# lab2_vodorezov_buck.net
KiCad netlist of a schematic drawn in Altium Designer
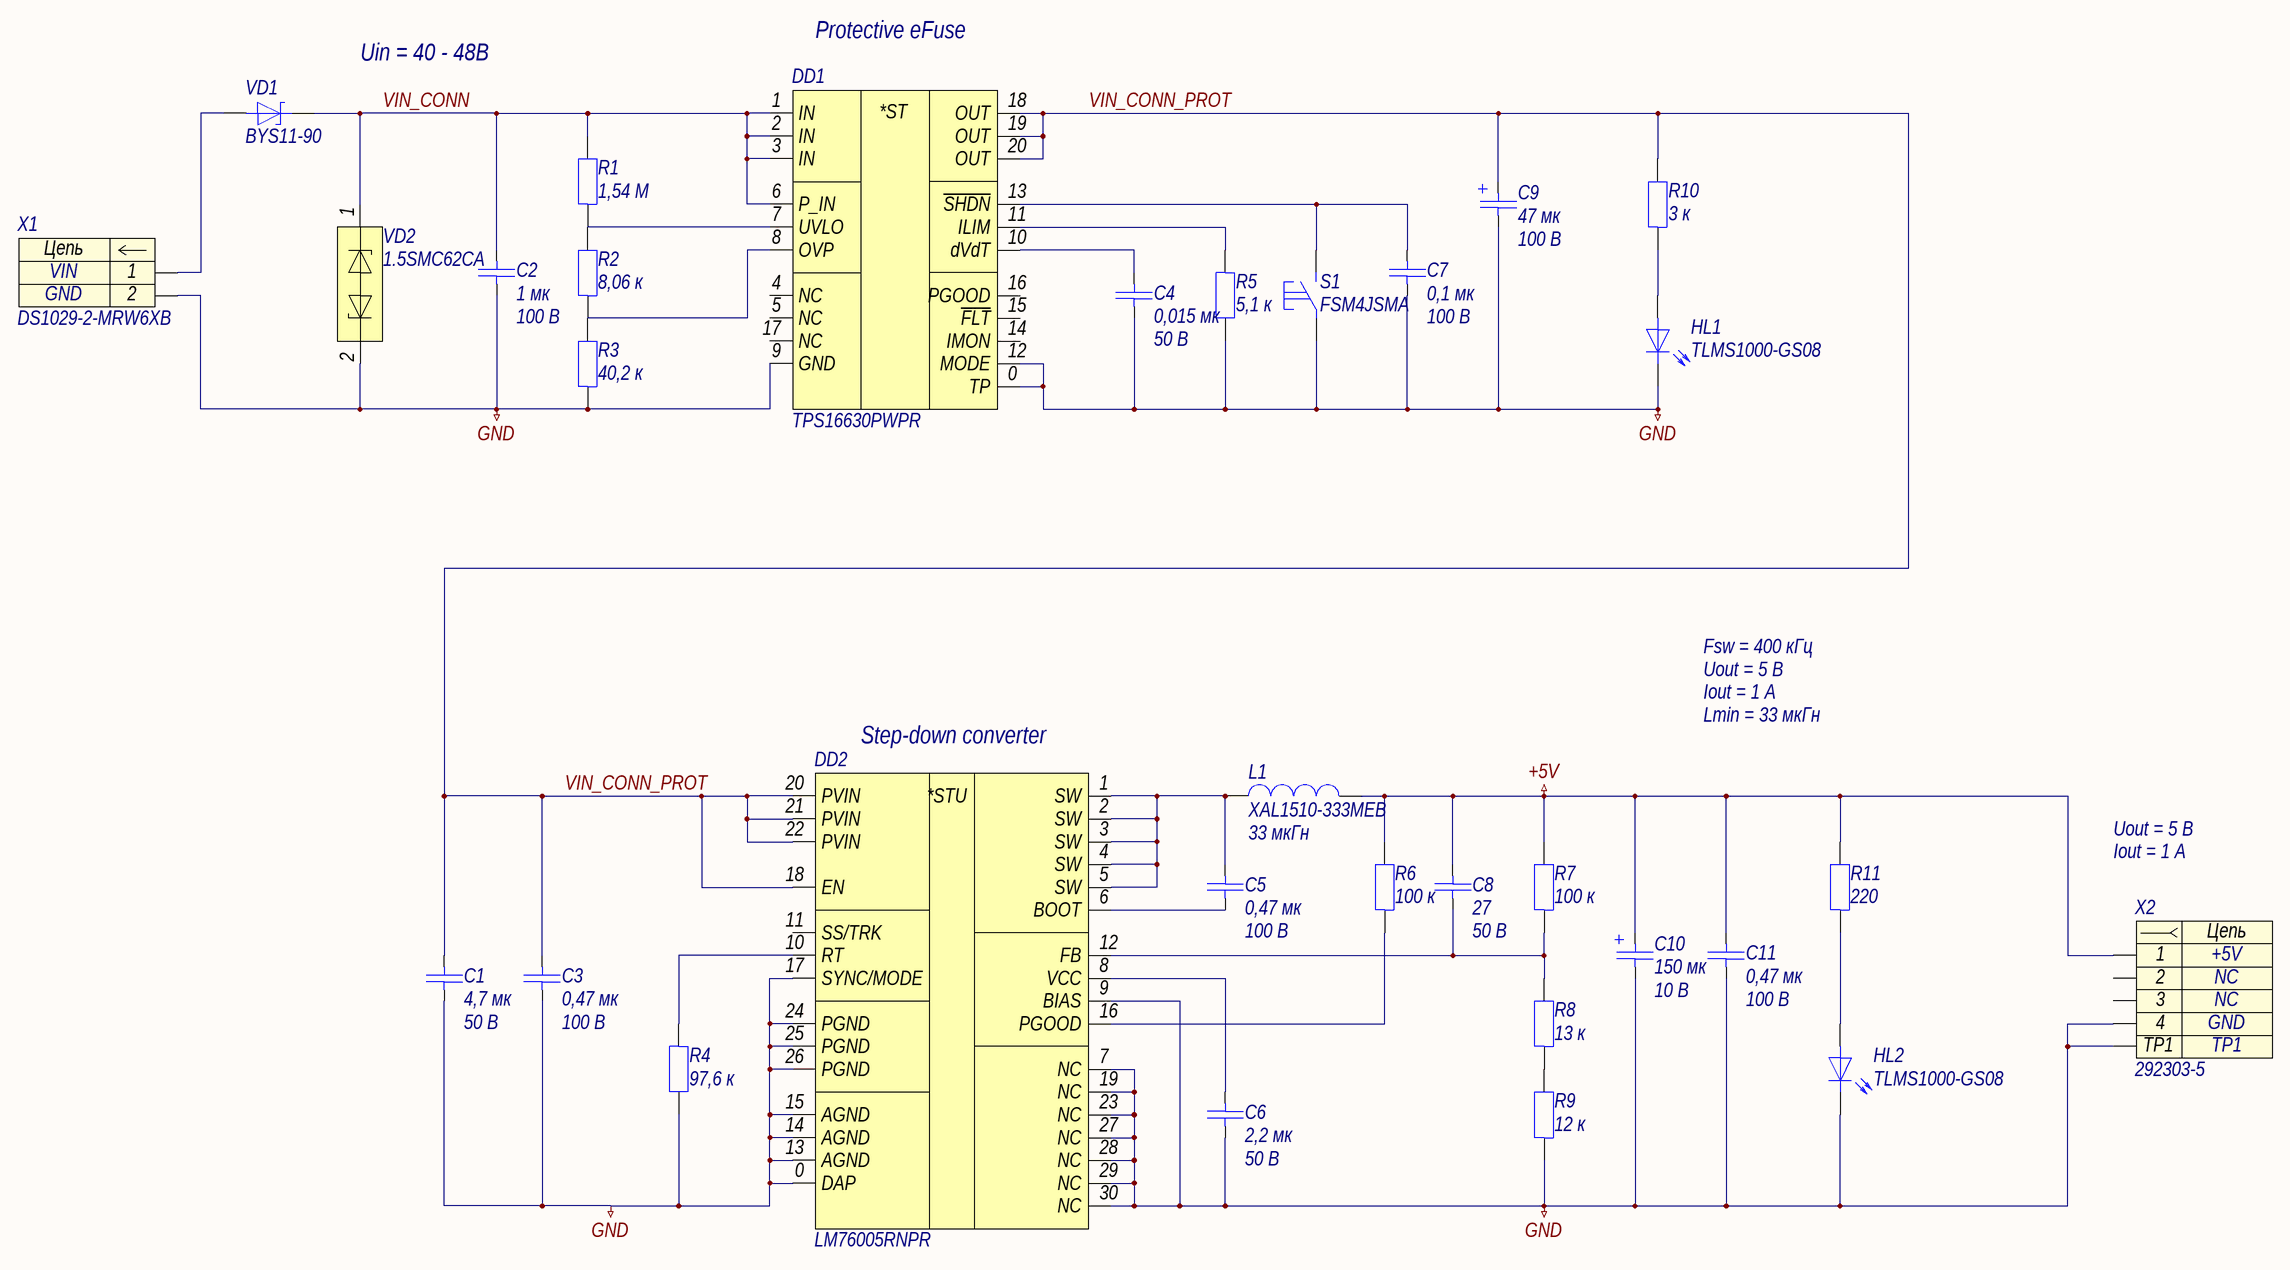
[diagram p0: lab2_vodorezov_buck.SchDoc]

(export (version "E")
  (design (tool "Eeschema 10.0.6"))
  (components
    (comp (ref "C1")
      (value "4,7 мк")
      (footprint "C1206")
      (description "=Описание")
      (fields (field (name "НАПРЯЖЕНИЕ") "50 В"))
      (libsource (lib "Database_Students") (part "C-NONPOLAR"))
    )
    (comp (ref "C2")
      (value "1 мк")
      (footprint "C1206")
      (description "=Описание")
      (fields (field (name "НАПРЯЖЕНИЕ") "100 В"))
      (libsource (lib "Database_Students") (part "C-NONPOLAR"))
    )
    (comp (ref "C3")
      (value "0,47 мк")
      (footprint "C1206")
      (description "=Описание")
      (fields (field (name "НАПРЯЖЕНИЕ") "100 В"))
      (libsource (lib "Database_Students") (part "C-NONPOLAR"))
    )
    (comp (ref "C4")
      (value "0,015 мк")
      (footprint "C0603")
      (description "=Описание")
      (fields (field (name "НАПРЯЖЕНИЕ") "50 В"))
      (libsource (lib "Database_Students") (part "C-NONPOLAR"))
    )
    (comp (ref "C5")
      (value "0,47 мк")
      (footprint "C1206")
      (description "=Описание")
      (fields (field (name "НАПРЯЖЕНИЕ") "100 В"))
      (libsource (lib "Database_Students") (part "C-NONPOLAR"))
    )
    (comp (ref "C6")
      (value "2,2 мк")
      (footprint "C0603")
      (description "=Описание")
      (fields (field (name "НАПРЯЖЕНИЕ") "50 В"))
      (libsource (lib "Database_Students") (part "C-NONPOLAR"))
    )
    (comp (ref "C7")
      (value "0,1 мк")
      (footprint "C0603")
      (description "=Описание")
      (fields (field (name "НАПРЯЖЕНИЕ") "100 В"))
      (libsource (lib "Database_Students") (part "C-NONPOLAR"))
    )
    (comp (ref "C8")
      (value "27")
      (footprint "C0402")
      (description "=Описание")
      (fields (field (name "НАПРЯЖЕНИЕ") "50 В"))
      (libsource (lib "Database_Students") (part "C-NONPOLAR"))
    )
    (comp (ref "C9")
      (value "47 мк")
      (footprint "CAPAE-1000X1000X1200")
      (description "=Описание")
      (fields (field (name "НАПРЯЖЕНИЕ") "100 В"))
      (libsource (lib "Database_Students") (part "C-POLAR"))
    )
    (comp (ref "C10")
      (value "150 мк")
      (footprint "CAPAE-660X660X580")
      (description "=Описание")
      (fields (field (name "НАПРЯЖЕНИЕ") "10 В"))
      (libsource (lib "Database_Students") (part "C-POLAR"))
    )
    (comp (ref "C11")
      (value "0,47 мк")
      (footprint "C1206")
      (description "=Описание")
      (fields (field (name "НАПРЯЖЕНИЕ") "100 В"))
      (libsource (lib "Database_Students") (part "C-NONPOLAR"))
    )
    (comp (ref "DD1")
      (value "TPS16630PWPR")
      (footprint "HTSSOP-20")
      (description "=Описание")
      (libsource (lib "Database_Students") (part "TPS16630PWPR"))
    )
    (comp (ref "DD2")
      (value "LM76005RNPR")
      (footprint "WQFN-30")
      (description "=Описание")
      (libsource (lib "Database_Students") (part "LM76005RNPR"))
    )
    (comp (ref "HL1")
      (value "TLMS1000-GS08")
      (footprint "HL0603")
      (description "=Описание")
      (libsource (lib "Database_Students") (part "HL-COMMON"))
    )
    (comp (ref "HL2")
      (value "TLMS1000-GS08")
      (footprint "HL0603")
      (description "=Описание")
      (libsource (lib "Database_Students") (part "HL-COMMON"))
    )
    (comp (ref "L1")
      (value "XAL1510-333MEB")
      (footprint "XAL-2-1620X1520X1100")
      (description "=Описание")
      (fields (field (name "ИНДУКТИВНОСТЬ") "33 мкГн"))
      (libsource (lib "Database_Students") (part "INDUCTOR-COMMON"))
    )
    (comp (ref "R1")
      (value "1,54 М")
      (footprint "R0603")
      (description "=Описание")
      (libsource (lib "Database_Students") (part "R-COMMON"))
    )
    (comp (ref "R2")
      (value "8,06 к")
      (footprint "R0603")
      (description "=Описание")
      (libsource (lib "Database_Students") (part "R-COMMON"))
    )
    (comp (ref "R3")
      (value "40,2 к")
      (footprint "R0603")
      (description "=Описание")
      (libsource (lib "Database_Students") (part "R-COMMON"))
    )
    (comp (ref "R4")
      (value "97,6 к")
      (footprint "R0603")
      (description "=Описание")
      (libsource (lib "Database_Students") (part "R-COMMON"))
    )
    (comp (ref "R5")
      (value "5,1 к")
      (footprint "R0603")
      (description "=Описание")
      (libsource (lib "Database_Students") (part "R-COMMON"))
    )
    (comp (ref "R6")
      (value "100 к")
      (footprint "R0603")
      (description "=Описание")
      (libsource (lib "Database_Students") (part "R-COMMON"))
    )
    (comp (ref "R7")
      (value "100 к")
      (footprint "R0603")
      (description "=Описание")
      (libsource (lib "Database_Students") (part "R-COMMON"))
    )
    (comp (ref "R8")
      (value "13 к")
      (footprint "R0603")
      (description "=Описание")
      (libsource (lib "Database_Students") (part "R-COMMON"))
    )
    (comp (ref "R9")
      (value "12 к")
      (footprint "R0603")
      (description "=Описание")
      (libsource (lib "Database_Students") (part "R-COMMON"))
    )
    (comp (ref "R10")
      (value "3 к")
      (footprint "R0603")
      (description "=Описание")
      (libsource (lib "Database_Students") (part "R-COMMON"))
    )
    (comp (ref "R11")
      (value "220")
      (footprint "R0603")
      (description "=Описание")
      (libsource (lib "Database_Students") (part "R-COMMON"))
    )
    (comp (ref "S1")
      (value "FSM4JSMA")
      (footprint "FSM4JSMA")
      (description "=Описание")
      (libsource (lib "Database_Students") (part "SWITCH-01"))
    )
    (comp (ref "VD1")
      (value "BYS11-90")
      (footprint "DO-214AC")
      (description "=Описание")
      (libsource (lib "Database_Students") (part "DIODE-SCHOTTKY"))
    )
    (comp (ref "VD2")
      (value "1.5SMC62CA")
      (footprint "DO-214AB")
      (description "=Описание")
      (libsource (lib "Database_Students") (part "ZENER-BI-DIRECTIONAL"))
    )
    (comp (ref "X1")
      (value "DS1029-2-MRW6XB")
      (footprint "DS1029-2-MRW6XB")
      (description "=Описание")
      (libsource (lib "Database_Students") (part "HEADER-2-PLG"))
    )
    (comp (ref "X2")
      (value "292303-5")
      (footprint "292303-5")
      (description "=Описание")
      (libsource (lib "Database_Students") (part "HEADER-4-TP1-SCT"))
    )
  )
  (nets
    (net (code "1") (name "+5V") (class "Default")
      (node (ref "C10") (pin "1") (pinfunction "1_1") (pintype "passive"))
      (node (ref "C11") (pin "1") (pinfunction "1_1") (pintype "passive"))
      (node (ref "C8") (pin "2") (pinfunction "2_2") (pintype "passive"))
      (node (ref "L1") (pin "2") (pinfunction "2_2") (pintype "passive"))
      (node (ref "R11") (pin "2") (pinfunction "2_2") (pintype "passive"))
      (node (ref "R6") (pin "2") (pinfunction "2_2") (pintype "passive"))
      (node (ref "R7") (pin "2") (pinfunction "2_2") (pintype "passive"))
      (node (ref "X2") (pin "1") (pinfunction "1_1") (pintype "passive"))
    )
    (net (code "2") (name "/VIN_CONN") (class "Default")
      (node (ref "C2") (pin "1") (pinfunction "1_1") (pintype "passive"))
      (node (ref "DD1") (pin "1") (pinfunction "IN_1") (pintype "passive"))
      (node (ref "DD1") (pin "2") (pinfunction "IN_2") (pintype "passive"))
      (node (ref "DD1") (pin "3") (pinfunction "IN_3") (pintype "passive"))
      (node (ref "DD1") (pin "6") (pinfunction "P_IN_6") (pintype "passive"))
      (node (ref "R1") (pin "2") (pinfunction "2_2") (pintype "passive"))
      (node (ref "VD1") (pin "1") (pinfunction "1_1") (pintype "passive"))
      (node (ref "VD2") (pin "1") (pinfunction "1_1") (pintype "passive"))
    )
    (net (code "3") (name "/VIN_CONN_PROT") (class "Default")
      (node (ref "C1") (pin "1") (pinfunction "1_1") (pintype "passive"))
      (node (ref "C3") (pin "1") (pinfunction "1_1") (pintype "passive"))
      (node (ref "C9") (pin "1") (pinfunction "1_1") (pintype "passive"))
      (node (ref "DD1") (pin "18") (pinfunction "OUT_18") (pintype "passive"))
      (node (ref "DD1") (pin "19") (pinfunction "OUT_19") (pintype "passive"))
      (node (ref "DD1") (pin "20") (pinfunction "OUT_20") (pintype "passive"))
      (node (ref "DD2") (pin "18") (pinfunction "EN_18") (pintype "passive"))
      (node (ref "DD2") (pin "20") (pinfunction "PVIN_20") (pintype "passive"))
      (node (ref "DD2") (pin "21") (pinfunction "PVIN_21") (pintype "passive"))
      (node (ref "DD2") (pin "22") (pinfunction "PVIN_22") (pintype "passive"))
      (node (ref "R10") (pin "2") (pinfunction "2_2") (pintype "passive"))
    )
    (net (code "4") (name "GND") (class "Default")
      (node (ref "C1") (pin "2") (pinfunction "2_2") (pintype "passive"))
      (node (ref "C10") (pin "2") (pinfunction "2_2") (pintype "passive"))
      (node (ref "C11") (pin "2") (pinfunction "2_2") (pintype "passive"))
      (node (ref "C2") (pin "2") (pinfunction "2_2") (pintype "passive"))
      (node (ref "C3") (pin "2") (pinfunction "2_2") (pintype "passive"))
      (node (ref "C4") (pin "2") (pinfunction "2_2") (pintype "passive"))
      (node (ref "C6") (pin "1") (pinfunction "1_1") (pintype "passive"))
      (node (ref "C7") (pin "2") (pinfunction "2_2") (pintype "passive"))
      (node (ref "C9") (pin "2") (pinfunction "2_2") (pintype "passive"))
      (node (ref "DD1") (pin "0") (pinfunction "TP_0") (pintype "passive"))
      (node (ref "DD1") (pin "12") (pinfunction "MODE_12") (pintype "passive"))
      (node (ref "DD1") (pin "9") (pinfunction "GND_9") (pintype "passive"))
      (node (ref "DD2") (pin "0") (pinfunction "DAP_0") (pintype "passive"))
      (node (ref "DD2") (pin "13") (pinfunction "AGND_13") (pintype "passive"))
      (node (ref "DD2") (pin "14") (pinfunction "AGND_14") (pintype "passive"))
      (node (ref "DD2") (pin "15") (pinfunction "AGND_15") (pintype "passive"))
      (node (ref "DD2") (pin "17") (pinfunction "SYNC/MODE_17") (pintype "passive"))
      (node (ref "DD2") (pin "19") (pinfunction "NC_19") (pintype "passive"))
      (node (ref "DD2") (pin "23") (pinfunction "NC_23") (pintype "passive"))
      (node (ref "DD2") (pin "24") (pinfunction "PGND_24") (pintype "passive"))
      (node (ref "DD2") (pin "25") (pinfunction "PGND_25") (pintype "passive"))
      (node (ref "DD2") (pin "26") (pinfunction "PGND_26") (pintype "passive"))
      (node (ref "DD2") (pin "27") (pinfunction "NC_27") (pintype "passive"))
      (node (ref "DD2") (pin "28") (pinfunction "NC_28") (pintype "passive"))
      (node (ref "DD2") (pin "29") (pinfunction "NC_29") (pintype "passive"))
      (node (ref "DD2") (pin "30") (pinfunction "NC_30") (pintype "passive"))
      (node (ref "DD2") (pin "7") (pinfunction "NC_7") (pintype "passive"))
      (node (ref "DD2") (pin "9") (pinfunction "BIAS_9") (pintype "passive"))
      (node (ref "HL1") (pin "1") (pinfunction "1_1") (pintype "passive"))
      (node (ref "HL2") (pin "1") (pinfunction "1_1") (pintype "passive"))
      (node (ref "R3") (pin "1") (pinfunction "1_1") (pintype "passive"))
      (node (ref "R4") (pin "2") (pinfunction "2_2") (pintype "passive"))
      (node (ref "R5") (pin "2") (pinfunction "2_2") (pintype "passive"))
      (node (ref "R9") (pin "1") (pinfunction "1_1") (pintype "passive"))
      (node (ref "S1") (pin "1") (pinfunction "1_1") (pintype "passive"))
      (node (ref "VD2") (pin "2") (pinfunction "2_2") (pintype "passive"))
      (node (ref "X1") (pin "2") (pinfunction "2_2") (pintype "passive"))
      (node (ref "X2") (pin "4") (pinfunction "4_4") (pintype "passive"))
      (node (ref "X2") (pin "TP1") (pinfunction "TP1_TP1") (pintype "passive"))
    )
    (net (code "5") (name "Net-(C5-Pad2)") (class "Default")
      (node (ref "C5") (pin "2") (pinfunction "2_2") (pintype "passive"))
      (node (ref "DD2") (pin "1") (pinfunction "SW_1") (pintype "passive"))
      (node (ref "DD2") (pin "2") (pinfunction "SW_2") (pintype "passive"))
      (node (ref "DD2") (pin "3") (pinfunction "SW_3") (pintype "passive"))
      (node (ref "DD2") (pin "4") (pinfunction "SW_4") (pintype "passive"))
      (node (ref "DD2") (pin "5") (pinfunction "SW_5") (pintype "passive"))
      (node (ref "L1") (pin "1") (pinfunction "1_1") (pintype "passive"))
    )
    (net (code "6") (name "Net-(DD1-ILIM)") (class "Default")
      (node (ref "DD1") (pin "11") (pinfunction "ILIM_11") (pintype "passive"))
      (node (ref "R5") (pin "1") (pinfunction "1_1") (pintype "passive"))
    )
    (net (code "7") (name "Net-(DD1-OVP)") (class "Default")
      (node (ref "DD1") (pin "8") (pinfunction "OVP_8") (pintype "passive"))
      (node (ref "R2") (pin "1") (pinfunction "1_1") (pintype "passive"))
      (node (ref "R3") (pin "2") (pinfunction "2_2") (pintype "passive"))
    )
    (net (code "8") (name "Net-(DD1-UVLO)") (class "Default")
      (node (ref "DD1") (pin "7") (pinfunction "UVLO_7") (pintype "passive"))
      (node (ref "R1") (pin "1") (pinfunction "1_1") (pintype "passive"))
      (node (ref "R2") (pin "2") (pinfunction "2_2") (pintype "passive"))
    )
    (net (code "9") (name "Net-(DD1-dVdT)") (class "Default")
      (node (ref "C4") (pin "1") (pinfunction "1_1") (pintype "passive"))
      (node (ref "DD1") (pin "10") (pinfunction "dVdT_10") (pintype "passive"))
    )
    (net (code "10") (name "Net-(DD1-~{SHDN})") (class "Default")
      (node (ref "C7") (pin "1") (pinfunction "1_1") (pintype "passive"))
      (node (ref "DD1") (pin "13") (pinfunction "~{SHDN}_13") (pintype "passive"))
      (node (ref "S1") (pin "2") (pinfunction "2_2") (pintype "passive"))
    )
    (net (code "11") (name "Net-(DD2-BOOT)") (class "Default")
      (node (ref "C5") (pin "1") (pinfunction "1_1") (pintype "passive"))
      (node (ref "DD2") (pin "6") (pinfunction "BOOT_6") (pintype "passive"))
    )
    (net (code "12") (name "Net-(DD2-FB)") (class "Default")
      (node (ref "C8") (pin "1") (pinfunction "1_1") (pintype "passive"))
      (node (ref "DD2") (pin "12") (pinfunction "FB_12") (pintype "passive"))
      (node (ref "R7") (pin "1") (pinfunction "1_1") (pintype "passive"))
      (node (ref "R8") (pin "2") (pinfunction "2_2") (pintype "passive"))
    )
    (net (code "13") (name "Net-(DD2-PGOOD)") (class "Default")
      (node (ref "DD2") (pin "16") (pinfunction "PGOOD_16") (pintype "passive"))
      (node (ref "R6") (pin "1") (pinfunction "1_1") (pintype "passive"))
    )
    (net (code "14") (name "Net-(DD2-RT)") (class "Default")
      (node (ref "DD2") (pin "10") (pinfunction "RT_10") (pintype "passive"))
      (node (ref "R4") (pin "1") (pinfunction "1_1") (pintype "passive"))
    )
    (net (code "15") (name "Net-(DD2-VCC)") (class "Default")
      (node (ref "C6") (pin "2") (pinfunction "2_2") (pintype "passive"))
      (node (ref "DD2") (pin "8") (pinfunction "VCC_8") (pintype "passive"))
    )
    (net (code "16") (name "Net-(HL1-Pad2)") (class "Default")
      (node (ref "HL1") (pin "2") (pinfunction "2_2") (pintype "passive"))
      (node (ref "R10") (pin "1") (pinfunction "1_1") (pintype "passive"))
    )
    (net (code "17") (name "Net-(HL2-Pad2)") (class "Default")
      (node (ref "HL2") (pin "2") (pinfunction "2_2") (pintype "passive"))
      (node (ref "R11") (pin "1") (pinfunction "1_1") (pintype "passive"))
    )
    (net (code "18") (name "Net-(R8-Pad1)") (class "Default")
      (node (ref "R8") (pin "1") (pinfunction "1_1") (pintype "passive"))
      (node (ref "R9") (pin "2") (pinfunction "2_2") (pintype "passive"))
    )
    (net (code "19") (name "Net-(VD1-Pad2)") (class "Default")
      (node (ref "VD1") (pin "2") (pinfunction "2_2") (pintype "passive"))
      (node (ref "X1") (pin "1") (pinfunction "1_1") (pintype "passive"))
    )
    (net (code "20") (name "unconnected-(DD1-IMON-Pad14)") (class "Default")
      (node (ref "DD1") (pin "14") (pinfunction "IMON_14") (pintype "passive"))
    )
    (net (code "21") (name "unconnected-(DD1-NC-Pad4)") (class "Default")
      (node (ref "DD1") (pin "4") (pinfunction "NC_4") (pintype "passive"))
    )
    (net (code "22") (name "unconnected-(DD1-NC-Pad5)") (class "Default")
      (node (ref "DD1") (pin "5") (pinfunction "NC_5") (pintype "passive"))
    )
    (net (code "23") (name "unconnected-(DD1-NC-Pad17)") (class "Default")
      (node (ref "DD1") (pin "17") (pinfunction "NC_17") (pintype "passive"))
    )
    (net (code "24") (name "unconnected-(DD1-PGOOD-Pad16)") (class "Default")
      (node (ref "DD1") (pin "16") (pinfunction "PGOOD_16") (pintype "passive"))
    )
    (net (code "25") (name "unconnected-(DD1-~{FLT}-Pad15)") (class "Default")
      (node (ref "DD1") (pin "15") (pinfunction "~{FLT}_15") (pintype "passive"))
    )
    (net (code "26") (name "unconnected-(DD2-SS{slash}TRK-Pad11)") (class "Default")
      (node (ref "DD2") (pin "11") (pinfunction "SS/TRK_11") (pintype "passive"))
    )
    (net (code "27") (name "unconnected-(X2-Pad2)") (class "Default")
      (node (ref "X2") (pin "2") (pinfunction "2_2") (pintype "passive"))
    )
    (net (code "28") (name "unconnected-(X2-Pad3)") (class "Default")
      (node (ref "X2") (pin "3") (pinfunction "3_3") (pintype "passive"))
    )
  )
)
